# piston_stm.net
KiCad netlist of a schematic drawn in EAGLE
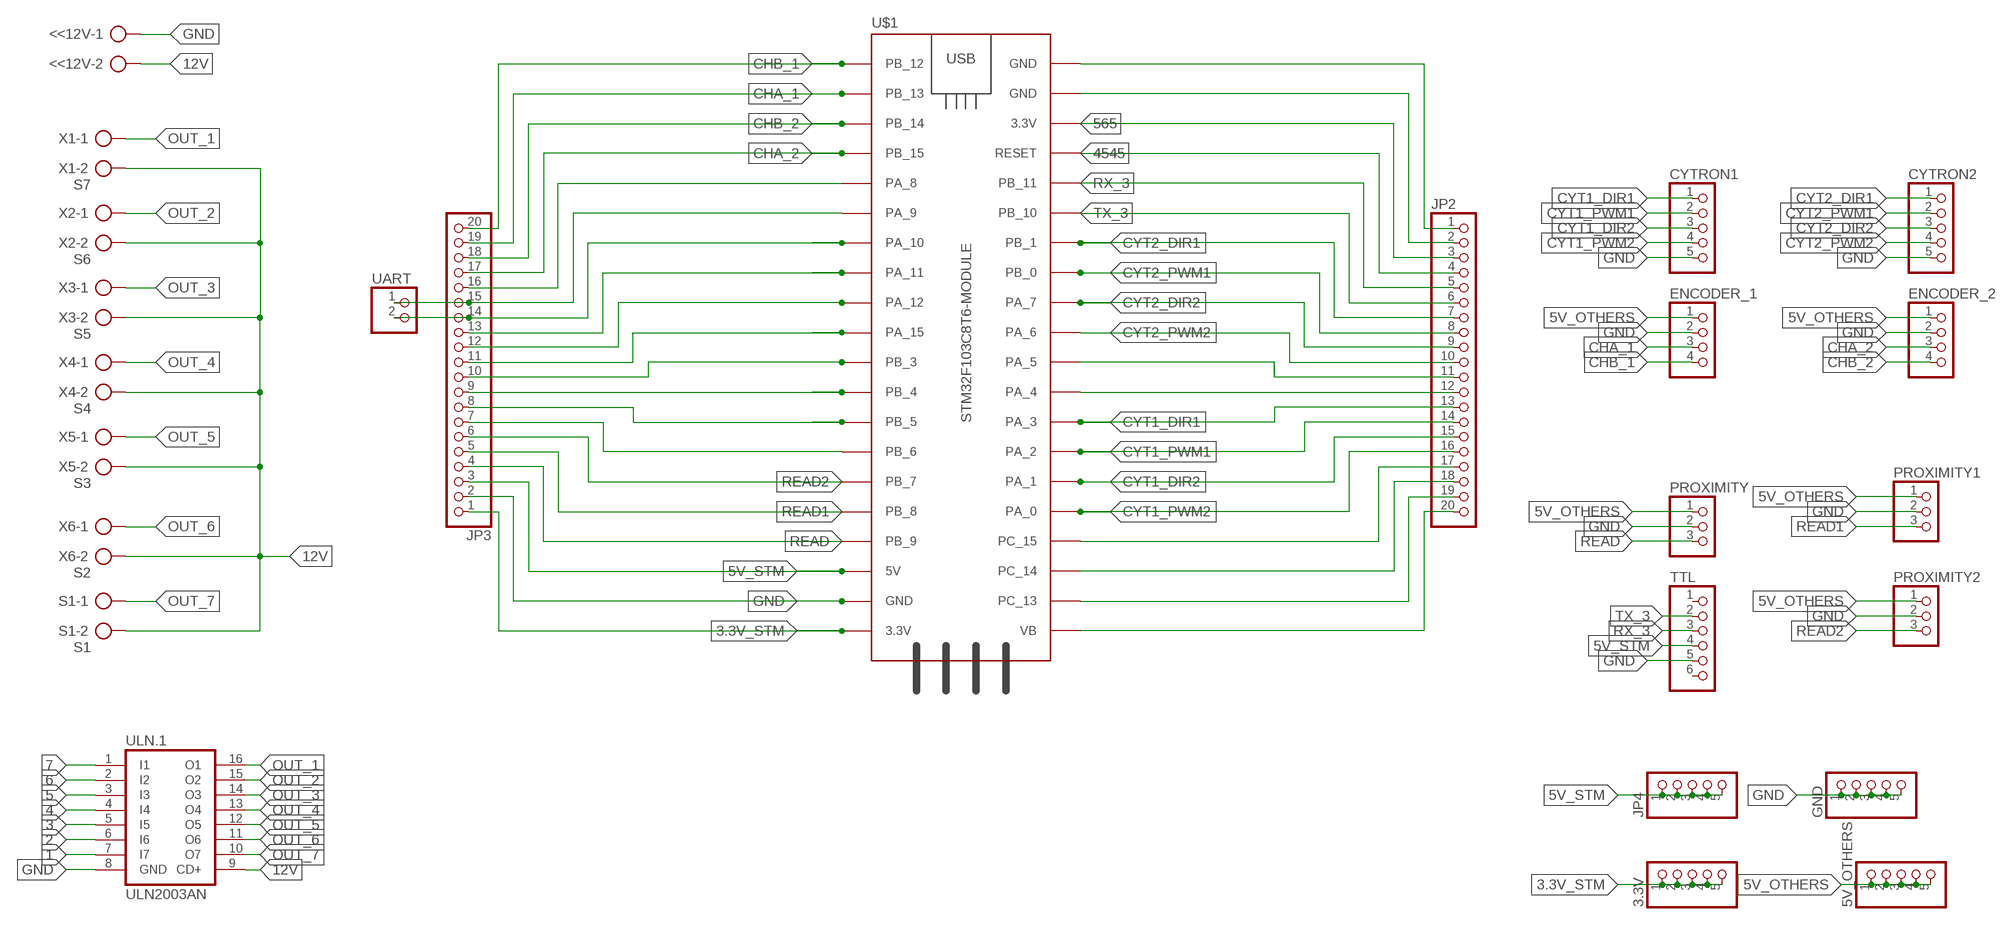
[diagram p0: schematic, sheet 1]

(export (version "E")
  (design (tool "Eeschema 10.0.6"))
  (components
    (comp (ref "3.3V")
      (value "PINHD-1X5")
      (footprint "eagle-import:1X05")
      (libsource (lib "eagle-import") (part "PINHD-1X5"))
    )
    (comp (ref "5V_OTHERS")
      (value "PINHD-1X5")
      (footprint "eagle-import:1X05")
      (libsource (lib "eagle-import") (part "PINHD-1X5"))
    )
    (comp (ref "<<12V")
      (value "AK300/2")
      (footprint "eagle-import:AK300_2")
      (libsource (lib "eagle-import") (part "AK300/2"))
    )
    (comp (ref "CYTRON1")
      (value "PINHD-5_DATA")
      (footprint "eagle-import:1X05_DATA")
      (libsource (lib "eagle-import") (part "PINHD-5_DATA"))
    )
    (comp (ref "CYTRON2")
      (value "PINHD-5_DATA")
      (footprint "eagle-import:1X05_DATA")
      (libsource (lib "eagle-import") (part "PINHD-5_DATA"))
    )
    (comp (ref "ENCODER_1")
      (value "PINHD-4_DATA")
      (footprint "eagle-import:1X04_DATA")
      (libsource (lib "eagle-import") (part "PINHD-4_DATA"))
    )
    (comp (ref "ENCODER_2")
      (value "PINHD-4_DATA")
      (footprint "eagle-import:1X04_DATA")
      (libsource (lib "eagle-import") (part "PINHD-4_DATA"))
    )
    (comp (ref "GND")
      (value "PINHD-1X5")
      (footprint "eagle-import:1X05")
      (libsource (lib "eagle-import") (part "PINHD-1X5"))
    )
    (comp (ref "JP2")
      (value "PINHD-1X20")
      (footprint "eagle-import:1X20")
      (libsource (lib "eagle-import") (part "PINHD-1X20"))
    )
    (comp (ref "JP3")
      (value "PINHD-1X20")
      (footprint "eagle-import:1X20")
      (libsource (lib "eagle-import") (part "PINHD-1X20"))
    )
    (comp (ref "JP4")
      (value "PINHD-1X5")
      (footprint "eagle-import:1X05")
      (libsource (lib "eagle-import") (part "PINHD-1X5"))
    )
    (comp (ref "PROXIMITY")
      (value "PINHD-3_DATA")
      (footprint "eagle-import:1X03_DATA")
      (libsource (lib "eagle-import") (part "PINHD-3_DATA"))
    )
    (comp (ref "PROXIMITY1")
      (value "PINHD-3_DATA")
      (footprint "eagle-import:1X03_DATA")
      (libsource (lib "eagle-import") (part "PINHD-3_DATA"))
    )
    (comp (ref "PROXIMITY2")
      (value "PINHD-3_DATA")
      (footprint "eagle-import:1X03_DATA")
      (libsource (lib "eagle-import") (part "PINHD-3_DATA"))
    )
    (comp (ref "S1")
      (value "S1")
      (footprint "eagle-import:AK300_2")
      (libsource (lib "eagle-import") (part "AK300/2"))
    )
    (comp (ref "TTL")
      (value "PINHD-6_DATA")
      (footprint "eagle-import:1X06_DATA")
      (libsource (lib "eagle-import") (part "PINHD-6_DATA"))
    )
    (comp (ref "U$1")
      (value "STM32F103C8T6-MODULE")
      (footprint "eagle-import:STM32F103C8T6-MODULE")
      (libsource (lib "eagle-import") (part "STM32F103C8T6-MODULE"))
    )
    (comp (ref "UART")
      (value "PINHD-2_DATA")
      (footprint "eagle-import:1X02_DATA")
      (libsource (lib "eagle-import") (part "PINHD-2_DATA"))
    )
    (comp (ref "ULN.1")
      (value "ULN2003AN")
      (footprint "eagle-import:DIL16")
      (libsource (lib "eagle-import") (part "ULN2003AN"))
    )
    (comp (ref "X1")
      (value "S7")
      (footprint "eagle-import:AK300_2")
      (libsource (lib "eagle-import") (part "AK300/2"))
    )
    (comp (ref "X2")
      (value "S6")
      (footprint "eagle-import:AK300_2")
      (libsource (lib "eagle-import") (part "AK300/2"))
    )
    (comp (ref "X3")
      (value "S5")
      (footprint "eagle-import:AK300_2")
      (libsource (lib "eagle-import") (part "AK300/2"))
    )
    (comp (ref "X4")
      (value "S4")
      (footprint "eagle-import:AK300_2")
      (libsource (lib "eagle-import") (part "AK300/2"))
    )
    (comp (ref "X5")
      (value "S3")
      (footprint "eagle-import:AK300_2")
      (libsource (lib "eagle-import") (part "AK300/2"))
    )
    (comp (ref "X6")
      (value "S2")
      (footprint "eagle-import:AK300_2")
      (libsource (lib "eagle-import") (part "AK300/2"))
    )
  )
  (nets
    (net (code "1") (name "1") (class "Default")
      (node (ref "JP3") (pin "13") (pinfunction "13_13") (pintype "passive"))
      (node (ref "U$1") (pin "PA_11") (pinfunction "PA_11_PA_11") (pintype "bidirectional"))
      (node (ref "ULN.1") (pin "7") (pinfunction "I7_7") (pintype "input"))
    )
    (net (code "2") (name "2") (class "Default")
      (node (ref "JP3") (pin "12") (pinfunction "12_12") (pintype "passive"))
      (node (ref "U$1") (pin "PA_12") (pinfunction "PA_12_PA_12") (pintype "bidirectional"))
      (node (ref "ULN.1") (pin "6") (pinfunction "I6_6") (pintype "input"))
    )
    (net (code "3") (name "3") (class "Default")
      (node (ref "JP3") (pin "11") (pinfunction "11_11") (pintype "passive"))
      (node (ref "U$1") (pin "PA_15") (pinfunction "PA_15_PA_15") (pintype "bidirectional"))
      (node (ref "ULN.1") (pin "5") (pinfunction "I5_5") (pintype "input"))
    )
    (net (code "4") (name "3.3V_STM") (class "Default")
      (node (ref "3.3V") (pin "1") (pinfunction "1_1") (pintype "passive"))
      (node (ref "3.3V") (pin "2") (pinfunction "2_2") (pintype "passive"))
      (node (ref "3.3V") (pin "3") (pinfunction "3_3") (pintype "passive"))
      (node (ref "3.3V") (pin "4") (pinfunction "4_4") (pintype "passive"))
      (node (ref "3.3V") (pin "5") (pinfunction "5_5") (pintype "passive"))
      (node (ref "JP3") (pin "1") (pinfunction "1_1") (pintype "passive"))
      (node (ref "U$1") (pin "3.3V_1") (pinfunction "3.3V_3.3V_1") (pintype "bidirectional"))
    )
    (net (code "5") (name "4") (class "Default")
      (node (ref "JP3") (pin "10") (pinfunction "10_10") (pintype "passive"))
      (node (ref "U$1") (pin "PB_3") (pinfunction "PB_3_PB_3") (pintype "bidirectional"))
      (node (ref "ULN.1") (pin "4") (pinfunction "I4_4") (pintype "input"))
    )
    (net (code "6") (name "5") (class "Default")
      (node (ref "JP3") (pin "9") (pinfunction "9_9") (pintype "passive"))
      (node (ref "U$1") (pin "PB_4") (pinfunction "PB_4_PB_4") (pintype "bidirectional"))
      (node (ref "ULN.1") (pin "3") (pinfunction "I3_3") (pintype "input"))
    )
    (net (code "7") (name "5V_OTHERS") (class "Default")
      (node (ref "5V_OTHERS") (pin "1") (pinfunction "1_1") (pintype "passive"))
      (node (ref "5V_OTHERS") (pin "2") (pinfunction "2_2") (pintype "passive"))
      (node (ref "5V_OTHERS") (pin "3") (pinfunction "3_3") (pintype "passive"))
      (node (ref "5V_OTHERS") (pin "4") (pinfunction "4_4") (pintype "passive"))
      (node (ref "5V_OTHERS") (pin "5") (pinfunction "5_5") (pintype "passive"))
      (node (ref "ENCODER_1") (pin "1") (pinfunction "1_1") (pintype "passive"))
      (node (ref "ENCODER_2") (pin "1") (pinfunction "1_1") (pintype "passive"))
      (node (ref "PROXIMITY") (pin "1") (pinfunction "1_1") (pintype "passive"))
      (node (ref "PROXIMITY1") (pin "1") (pinfunction "1_1") (pintype "passive"))
      (node (ref "PROXIMITY2") (pin "1") (pinfunction "1_1") (pintype "passive"))
    )
    (net (code "8") (name "5V_STM") (class "Default")
      (node (ref "JP3") (pin "3") (pinfunction "3_3") (pintype "passive"))
      (node (ref "JP4") (pin "1") (pinfunction "1_1") (pintype "passive"))
      (node (ref "JP4") (pin "2") (pinfunction "2_2") (pintype "passive"))
      (node (ref "JP4") (pin "3") (pinfunction "3_3") (pintype "passive"))
      (node (ref "JP4") (pin "4") (pinfunction "4_4") (pintype "passive"))
      (node (ref "JP4") (pin "5") (pinfunction "5_5") (pintype "passive"))
      (node (ref "TTL") (pin "4") (pinfunction "4_4") (pintype "passive"))
      (node (ref "U$1") (pin "5V") (pinfunction "5V_5V") (pintype "bidirectional"))
    )
    (net (code "9") (name "6") (class "Default")
      (node (ref "JP3") (pin "8") (pinfunction "8_8") (pintype "passive"))
      (node (ref "U$1") (pin "PB_5") (pinfunction "PB_5_PB_5") (pintype "bidirectional"))
      (node (ref "ULN.1") (pin "2") (pinfunction "I2_2") (pintype "input"))
    )
    (net (code "10") (name "7") (class "Default")
      (node (ref "JP2") (pin "12") (pinfunction "12_12") (pintype "passive"))
      (node (ref "U$1") (pin "PA_4") (pinfunction "PA_4_PA_4") (pintype "bidirectional"))
      (node (ref "ULN.1") (pin "1") (pinfunction "I1_1") (pintype "input"))
    )
    (net (code "11") (name "12V") (class "Default")
      (node (ref "<<12V") (pin "2") (pinfunction "KL_2") (pintype "passive"))
      (node (ref "S1") (pin "2") (pinfunction "KL_2") (pintype "passive"))
      (node (ref "ULN.1") (pin "9") (pinfunction "CD+_9") (pintype "passive"))
      (node (ref "X1") (pin "2") (pinfunction "KL_2") (pintype "passive"))
      (node (ref "X2") (pin "2") (pinfunction "KL_2") (pintype "passive"))
      (node (ref "X3") (pin "2") (pinfunction "KL_2") (pintype "passive"))
      (node (ref "X4") (pin "2") (pinfunction "KL_2") (pintype "passive"))
      (node (ref "X5") (pin "2") (pinfunction "KL_2") (pintype "passive"))
      (node (ref "X6") (pin "2") (pinfunction "KL_2") (pintype "passive"))
    )
    (net (code "12") (name "565") (class "Default")
      (node (ref "JP2") (pin "3") (pinfunction "3_3") (pintype "passive"))
      (node (ref "U$1") (pin "3.3V_2") (pinfunction "3.3V_3.3V_2") (pintype "bidirectional"))
    )
    (net (code "13") (name "4545") (class "Default")
      (node (ref "JP2") (pin "4") (pinfunction "4_4") (pintype "passive"))
      (node (ref "U$1") (pin "RESET") (pinfunction "RESET_RESET") (pintype "bidirectional"))
    )
    (net (code "14") (name "CHA_1") (class "Default")
      (node (ref "ENCODER_1") (pin "3") (pinfunction "3_3") (pintype "passive"))
      (node (ref "JP3") (pin "19") (pinfunction "19_19") (pintype "passive"))
      (node (ref "U$1") (pin "PB_13") (pinfunction "PB_13_PB_13") (pintype "bidirectional"))
    )
    (net (code "15") (name "CHA_2") (class "Default")
      (node (ref "ENCODER_2") (pin "3") (pinfunction "3_3") (pintype "passive"))
      (node (ref "JP3") (pin "17") (pinfunction "17_17") (pintype "passive"))
      (node (ref "U$1") (pin "PB_15") (pinfunction "PB_15_PB_15") (pintype "bidirectional"))
    )
    (net (code "16") (name "CHB_1") (class "Default")
      (node (ref "ENCODER_1") (pin "4") (pinfunction "4_4") (pintype "passive"))
      (node (ref "JP3") (pin "20") (pinfunction "20_20") (pintype "passive"))
      (node (ref "U$1") (pin "PB_12") (pinfunction "PB_12_PB_12") (pintype "bidirectional"))
    )
    (net (code "17") (name "CHB_2") (class "Default")
      (node (ref "ENCODER_2") (pin "4") (pinfunction "4_4") (pintype "passive"))
      (node (ref "JP3") (pin "18") (pinfunction "18_18") (pintype "passive"))
      (node (ref "U$1") (pin "PB_14") (pinfunction "PB_14_PB_14") (pintype "bidirectional"))
    )
    (net (code "18") (name "CYT1_DIR1") (class "Default")
      (node (ref "CYTRON1") (pin "1") (pinfunction "1_1") (pintype "passive"))
      (node (ref "JP2") (pin "13") (pinfunction "13_13") (pintype "passive"))
      (node (ref "U$1") (pin "PA_3") (pinfunction "PA_3_PA_3") (pintype "bidirectional"))
    )
    (net (code "19") (name "CYT1_DIR2") (class "Default")
      (node (ref "CYTRON1") (pin "3") (pinfunction "3_3") (pintype "passive"))
      (node (ref "JP2") (pin "15") (pinfunction "15_15") (pintype "passive"))
      (node (ref "U$1") (pin "PA_1") (pinfunction "PA_1_PA_1") (pintype "bidirectional"))
    )
    (net (code "20") (name "CYT1_PWM1") (class "Default")
      (node (ref "CYTRON1") (pin "2") (pinfunction "2_2") (pintype "passive"))
      (node (ref "JP2") (pin "14") (pinfunction "14_14") (pintype "passive"))
      (node (ref "U$1") (pin "PA_2") (pinfunction "PA_2_PA_2") (pintype "bidirectional"))
    )
    (net (code "21") (name "CYT1_PWM2") (class "Default")
      (node (ref "CYTRON1") (pin "4") (pinfunction "4_4") (pintype "passive"))
      (node (ref "JP2") (pin "16") (pinfunction "16_16") (pintype "passive"))
      (node (ref "U$1") (pin "PA_0") (pinfunction "PA_0_PA_0") (pintype "bidirectional"))
    )
    (net (code "22") (name "CYT2_DIR1") (class "Default")
      (node (ref "CYTRON2") (pin "1") (pinfunction "1_1") (pintype "passive"))
      (node (ref "JP2") (pin "7") (pinfunction "7_7") (pintype "passive"))
      (node (ref "U$1") (pin "PB_1") (pinfunction "PB_1_PB_1") (pintype "bidirectional"))
    )
    (net (code "23") (name "CYT2_DIR2") (class "Default")
      (node (ref "CYTRON2") (pin "3") (pinfunction "3_3") (pintype "passive"))
      (node (ref "JP2") (pin "9") (pinfunction "9_9") (pintype "passive"))
      (node (ref "U$1") (pin "PA_7") (pinfunction "PA_7_PA_7") (pintype "bidirectional"))
    )
    (net (code "24") (name "CYT2_PWM1") (class "Default")
      (node (ref "CYTRON2") (pin "2") (pinfunction "2_2") (pintype "passive"))
      (node (ref "JP2") (pin "8") (pinfunction "8_8") (pintype "passive"))
      (node (ref "U$1") (pin "PB_0") (pinfunction "PB_0_PB_0") (pintype "bidirectional"))
    )
    (net (code "25") (name "CYT2_PWM2") (class "Default")
      (node (ref "CYTRON2") (pin "4") (pinfunction "4_4") (pintype "passive"))
      (node (ref "JP2") (pin "10") (pinfunction "10_10") (pintype "passive"))
      (node (ref "U$1") (pin "PA_6") (pinfunction "PA_6_PA_6") (pintype "bidirectional"))
    )
    (net (code "26") (name "GND") (class "Default")
      (node (ref "<<12V") (pin "1") (pinfunction "KL_1") (pintype "passive"))
      (node (ref "CYTRON1") (pin "5") (pinfunction "5_5") (pintype "passive"))
      (node (ref "CYTRON2") (pin "5") (pinfunction "5_5") (pintype "passive"))
      (node (ref "ENCODER_1") (pin "2") (pinfunction "2_2") (pintype "passive"))
      (node (ref "ENCODER_2") (pin "2") (pinfunction "2_2") (pintype "passive"))
      (node (ref "GND") (pin "1") (pinfunction "1_1") (pintype "passive"))
      (node (ref "GND") (pin "2") (pinfunction "2_2") (pintype "passive"))
      (node (ref "GND") (pin "3") (pinfunction "3_3") (pintype "passive"))
      (node (ref "GND") (pin "4") (pinfunction "4_4") (pintype "passive"))
      (node (ref "GND") (pin "5") (pinfunction "5_5") (pintype "passive"))
      (node (ref "JP2") (pin "1") (pinfunction "1_1") (pintype "passive"))
      (node (ref "JP2") (pin "2") (pinfunction "2_2") (pintype "passive"))
      (node (ref "JP3") (pin "2") (pinfunction "2_2") (pintype "passive"))
      (node (ref "PROXIMITY") (pin "2") (pinfunction "2_2") (pintype "passive"))
      (node (ref "PROXIMITY1") (pin "2") (pinfunction "2_2") (pintype "passive"))
      (node (ref "PROXIMITY2") (pin "2") (pinfunction "2_2") (pintype "passive"))
      (node (ref "TTL") (pin "5") (pinfunction "5_5") (pintype "passive"))
      (node (ref "U$1") (pin "GND_1") (pinfunction "GND_GND_1") (pintype "bidirectional"))
      (node (ref "U$1") (pin "GND_2") (pinfunction "GND_GND_2") (pintype "bidirectional"))
      (node (ref "U$1") (pin "GND_3") (pinfunction "GND_GND_3") (pintype "power_in"))
      (node (ref "ULN.1") (pin "8") (pinfunction "GND_8") (pintype "power_in"))
    )
    (net (code "27") (name "Net-(JP2-Pad11)") (class "Default")
      (node (ref "JP2") (pin "11") (pinfunction "11_11") (pintype "passive"))
      (node (ref "U$1") (pin "PA_5") (pinfunction "PA_5_PA_5") (pintype "bidirectional"))
    )
    (net (code "28") (name "Net-(JP2-Pad17)") (class "Default")
      (node (ref "JP2") (pin "17") (pinfunction "17_17") (pintype "passive"))
      (node (ref "U$1") (pin "PC_15") (pinfunction "PC_15_PC_15") (pintype "bidirectional"))
    )
    (net (code "29") (name "Net-(JP2-Pad18)") (class "Default")
      (node (ref "JP2") (pin "18") (pinfunction "18_18") (pintype "passive"))
      (node (ref "U$1") (pin "PC_14") (pinfunction "PC_14_PC_14") (pintype "bidirectional"))
    )
    (net (code "30") (name "Net-(JP2-Pad19)") (class "Default")
      (node (ref "JP2") (pin "19") (pinfunction "19_19") (pintype "passive"))
      (node (ref "U$1") (pin "PC_13") (pinfunction "PC_13_PC_13") (pintype "bidirectional"))
    )
    (net (code "31") (name "Net-(JP2-Pad20)") (class "Default")
      (node (ref "JP2") (pin "20") (pinfunction "20_20") (pintype "passive"))
      (node (ref "U$1") (pin "VB") (pinfunction "VB_VB") (pintype "bidirectional"))
    )
    (net (code "32") (name "Net-(JP3-Pad7)") (class "Default")
      (node (ref "JP3") (pin "7") (pinfunction "7_7") (pintype "passive"))
      (node (ref "U$1") (pin "PB_6") (pinfunction "PB_6_PB_6") (pintype "bidirectional"))
    )
    (net (code "33") (name "Net-(JP3-Pad14)") (class "Default")
      (node (ref "JP3") (pin "14") (pinfunction "14_14") (pintype "passive"))
      (node (ref "U$1") (pin "PA_10") (pinfunction "PA_10_PA_10") (pintype "bidirectional"))
      (node (ref "UART") (pin "2") (pinfunction "2_2") (pintype "passive"))
    )
    (net (code "34") (name "Net-(JP3-Pad15)") (class "Default")
      (node (ref "JP3") (pin "15") (pinfunction "15_15") (pintype "passive"))
      (node (ref "U$1") (pin "PA_9") (pinfunction "PA_9_PA_9") (pintype "bidirectional"))
      (node (ref "UART") (pin "1") (pinfunction "1_1") (pintype "passive"))
    )
    (net (code "35") (name "Net-(JP3-Pad16)") (class "Default")
      (node (ref "JP3") (pin "16") (pinfunction "16_16") (pintype "passive"))
      (node (ref "U$1") (pin "PA_8") (pinfunction "PA_8_PA_8") (pintype "bidirectional"))
    )
    (net (code "36") (name "OUT_1") (class "Default")
      (node (ref "ULN.1") (pin "16") (pinfunction "O1_16") (pintype "open_collector"))
      (node (ref "X1") (pin "1") (pinfunction "KL_1") (pintype "passive"))
    )
    (net (code "37") (name "OUT_2") (class "Default")
      (node (ref "ULN.1") (pin "15") (pinfunction "O2_15") (pintype "open_collector"))
      (node (ref "X2") (pin "1") (pinfunction "KL_1") (pintype "passive"))
    )
    (net (code "38") (name "OUT_3") (class "Default")
      (node (ref "ULN.1") (pin "14") (pinfunction "O3_14") (pintype "open_collector"))
      (node (ref "X3") (pin "1") (pinfunction "KL_1") (pintype "passive"))
    )
    (net (code "39") (name "OUT_4") (class "Default")
      (node (ref "ULN.1") (pin "13") (pinfunction "O4_13") (pintype "open_collector"))
      (node (ref "X4") (pin "1") (pinfunction "KL_1") (pintype "passive"))
    )
    (net (code "40") (name "OUT_5") (class "Default")
      (node (ref "ULN.1") (pin "12") (pinfunction "O5_12") (pintype "open_collector"))
      (node (ref "X5") (pin "1") (pinfunction "KL_1") (pintype "passive"))
    )
    (net (code "41") (name "OUT_6") (class "Default")
      (node (ref "ULN.1") (pin "11") (pinfunction "O6_11") (pintype "open_collector"))
      (node (ref "X6") (pin "1") (pinfunction "KL_1") (pintype "passive"))
    )
    (net (code "42") (name "OUT_7") (class "Default")
      (node (ref "S1") (pin "1") (pinfunction "KL_1") (pintype "passive"))
      (node (ref "ULN.1") (pin "10") (pinfunction "O7_10") (pintype "open_collector"))
    )
    (net (code "43") (name "READ") (class "Default")
      (node (ref "JP3") (pin "4") (pinfunction "4_4") (pintype "passive"))
      (node (ref "PROXIMITY") (pin "3") (pinfunction "3_3") (pintype "passive"))
      (node (ref "U$1") (pin "PB_9") (pinfunction "PB_9_PB_9") (pintype "bidirectional"))
    )
    (net (code "44") (name "READ1") (class "Default")
      (node (ref "JP3") (pin "5") (pinfunction "5_5") (pintype "passive"))
      (node (ref "PROXIMITY1") (pin "3") (pinfunction "3_3") (pintype "passive"))
      (node (ref "U$1") (pin "PB_8") (pinfunction "PB_8_PB_8") (pintype "bidirectional"))
    )
    (net (code "45") (name "READ2") (class "Default")
      (node (ref "JP3") (pin "6") (pinfunction "6_6") (pintype "passive"))
      (node (ref "PROXIMITY2") (pin "3") (pinfunction "3_3") (pintype "passive"))
      (node (ref "U$1") (pin "PB_7") (pinfunction "PB_7_PB_7") (pintype "bidirectional"))
    )
    (net (code "46") (name "RX_3") (class "Default")
      (node (ref "JP2") (pin "5") (pinfunction "5_5") (pintype "passive"))
      (node (ref "TTL") (pin "3") (pinfunction "3_3") (pintype "passive"))
      (node (ref "U$1") (pin "PB_11") (pinfunction "PB_11_PB_11") (pintype "bidirectional"))
    )
    (net (code "47") (name "TX_3") (class "Default")
      (node (ref "JP2") (pin "6") (pinfunction "6_6") (pintype "passive"))
      (node (ref "TTL") (pin "2") (pinfunction "2_2") (pintype "passive"))
      (node (ref "U$1") (pin "PB_10") (pinfunction "PB_10_PB_10") (pintype "bidirectional"))
    )
    (net (code "48") (name "unconnected-(TTL-Pad1)") (class "Default")
      (node (ref "TTL") (pin "1") (pinfunction "1_1") (pintype "passive"))
    )
    (net (code "49") (name "unconnected-(TTL-Pad6)") (class "Default")
      (node (ref "TTL") (pin "6") (pinfunction "6_6") (pintype "passive"))
    )
  )
)
